# design.net
KiCad netlist of a schematic drawn in Altium Designer
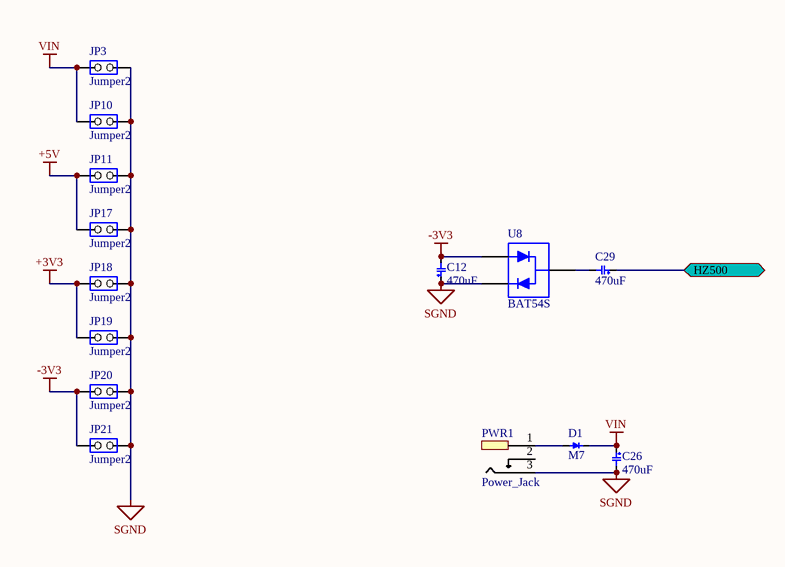
[diagram p0: 电源.SchDoc]

(export (version "E")
  (design (tool "Eeschema 10.0.6"))
  (components
    (comp (ref "C12")
      (value "470uF")
      (footprint "电容卧P2.54-D6.3-H7")
      (description "极性电容")
      (fields (field (name "PUBLISHER") "Altium Limited"))
      (libsource (lib "Miscellaneous Devices") (part "Cap Pol"))
    )
    (comp (ref "C26")
      (value "470uF")
      (footprint "电容卧P3.5-D8-H11.5")
      (description "极性电容")
      (fields (field (name "PUBLISHER") "Altium Limited"))
      (libsource (lib "Miscellaneous Devices") (part "Cap Pol"))
    )
    (comp (ref "C29")
      (value "470uF")
      (footprint "电容卧P2.54-D6.3-H7")
      (description "极性电容")
      (fields (field (name "PUBLISHER") "Altium Limited"))
      (libsource (lib "Miscellaneous Devices") (part "Cap Pol"))
    )
    (comp (ref "D1")
      (value "M7")
      (footprint "SMA")
      (description "二极管")
      (fields (field (name "PUBLISHER") "Altium Limited"))
      (libsource (lib "Miscellaneous Devices") (part "Diode"))
    )
    (comp (ref "JP3")
      (value "Jumper2")
      (footprint "CON2-P2.54")
      (libsource (lib "Miscellaneous Connectors") (part "Jumper2"))
    )
    (comp (ref "JP10")
      (value "Jumper2")
      (footprint "CON2-P2.54")
      (libsource (lib "Miscellaneous Connectors") (part "Jumper2"))
    )
    (comp (ref "JP11")
      (value "Jumper2")
      (footprint "CON2-P2.54")
      (libsource (lib "Miscellaneous Connectors") (part "Jumper2"))
    )
    (comp (ref "JP17")
      (value "Jumper2")
      (footprint "CON2-P2.54")
      (libsource (lib "Miscellaneous Connectors") (part "Jumper2"))
    )
    (comp (ref "JP18")
      (value "Jumper2")
      (footprint "CON2-P2.54")
      (libsource (lib "Miscellaneous Connectors") (part "Jumper2"))
    )
    (comp (ref "JP19")
      (value "Jumper2")
      (footprint "CON2-P2.54")
      (libsource (lib "Miscellaneous Connectors") (part "Jumper2"))
    )
    (comp (ref "JP20")
      (value "Jumper2")
      (footprint "CON2-P2.54")
      (libsource (lib "Miscellaneous Connectors") (part "Jumper2"))
    )
    (comp (ref "JP21")
      (value "Jumper2")
      (footprint "CON2-P2.54")
      (libsource (lib "Miscellaneous Connectors") (part "Jumper2"))
    )
    (comp (ref "PWR1")
      (value "Power_Jack")
      (footprint "Jack 2.1")
      (description "DC Power Jack")
      (fields (field (name "MANUFACTURER") "Switchcraft"))
      (libsource (lib "Miscellaneous Connectors") (part "Power_Jack"))
    )
    (comp (ref "U8")
      (value "BAT54S")
      (footprint "SOT-23-3L")
      (libsource (lib "Miscellaneous Devices") (part "diode BAT54S"))
    )
  )
  (nets
    (net (code "1") (name "+3V3") (class "Default")
      (node (ref "JP18") (pin "1") (pinfunction "COMMON_1") (pintype "passive"))
      (node (ref "JP19") (pin "1") (pinfunction "COMMON_1") (pintype "passive"))
    )
    (net (code "2") (name "+5V") (class "Default")
      (node (ref "JP11") (pin "1") (pinfunction "COMMON_1") (pintype "passive"))
      (node (ref "JP17") (pin "1") (pinfunction "COMMON_1") (pintype "passive"))
    )
    (net (code "3") (name "-3V3") (class "Default")
      (node (ref "C12") (pin "2") (pinfunction "2_2") (pintype "passive"))
      (node (ref "JP20") (pin "1") (pinfunction "COMMON_1") (pintype "passive"))
      (node (ref "JP21") (pin "1") (pinfunction "COMMON_1") (pintype "passive"))
      (node (ref "U8") (pin "1") (pinfunction "1_1") (pintype "passive"))
    )
    (net (code "4") (name "/HZ500") (class "Default")
      (node (ref "C29") (pin "1") (pinfunction "1_1") (pintype "passive"))
    )
    (net (code "5") (name "Net-(C29-Pad2)") (class "Default")
      (node (ref "C29") (pin "2") (pinfunction "2_2") (pintype "passive"))
      (node (ref "U8") (pin "3") (pinfunction "3_3") (pintype "passive"))
    )
    (net (code "6") (name "Net-(D1-Pad2)") (class "Default")
      (node (ref "D1") (pin "2") (pinfunction "2_2") (pintype "passive"))
      (node (ref "PWR1") (pin "1") (pinfunction "1_1") (pintype "passive"))
    )
    (net (code "7") (name "SGND") (class "Default")
      (node (ref "C12") (pin "1") (pinfunction "1_1") (pintype "passive"))
      (node (ref "C26") (pin "2") (pinfunction "2_2") (pintype "passive"))
      (node (ref "JP10") (pin "2") (pinfunction "NO_2") (pintype "passive"))
      (node (ref "JP11") (pin "2") (pinfunction "NO_2") (pintype "passive"))
      (node (ref "JP17") (pin "2") (pinfunction "NO_2") (pintype "passive"))
      (node (ref "JP18") (pin "2") (pinfunction "NO_2") (pintype "passive"))
      (node (ref "JP19") (pin "2") (pinfunction "NO_2") (pintype "passive"))
      (node (ref "JP20") (pin "2") (pinfunction "NO_2") (pintype "passive"))
      (node (ref "JP21") (pin "2") (pinfunction "NO_2") (pintype "passive"))
      (node (ref "JP3") (pin "2") (pinfunction "NO_2") (pintype "passive"))
      (node (ref "PWR1") (pin "3") (pinfunction "3_3") (pintype "passive"))
      (node (ref "U8") (pin "2") (pinfunction "2_2") (pintype "passive"))
    )
    (net (code "8") (name "VIN") (class "Default")
      (node (ref "C26") (pin "1") (pinfunction "1_1") (pintype "passive"))
      (node (ref "D1") (pin "1") (pinfunction "1_1") (pintype "passive"))
      (node (ref "JP10") (pin "1") (pinfunction "COMMON_1") (pintype "passive"))
      (node (ref "JP3") (pin "1") (pinfunction "COMMON_1") (pintype "passive"))
    )
    (net (code "9") (name "unconnected-(PWR1-Pad2)") (class "Default")
      (node (ref "PWR1") (pin "2") (pinfunction "2_2") (pintype "passive"))
    )
  )
)
